# Seperation_Switches.net
KiCad netlist of a schematic drawn in Altium Designer
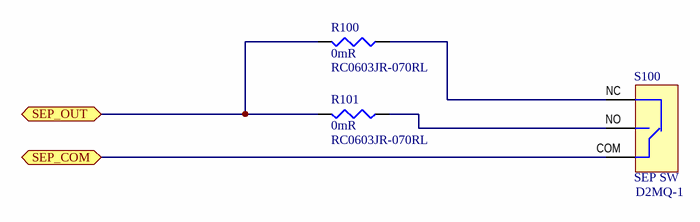
[diagram p0: Seperation Switches.SchDoc]

(export (version "E")
  (design (tool "Eeschema 10.0.6"))
  (components
    (comp (ref "R100")
      (value "0mR")
      (footprint "0603")
      (description "RES SMD 0 OHM JUMPER 1/10W 0603")
      (fields (field (name "MANUFACTURER PART NUMBER 1") "RC0603JR-070RL") (field (name "TOLERANCE") "1%"))
      (libsource (lib "CubeSat-Backplane") (part "RES1"))
    )
    (comp (ref "R101")
      (value "0mR")
      (footprint "0603")
      (description "RES SMD 0 OHM JUMPER 1/10W 0603")
      (fields (field (name "MANUFACTURER PART NUMBER 1") "RC0603JR-070RL") (field (name "TOLERANCE") "1%"))
      (libsource (lib "CubeSat-Backplane") (part "RES1"))
    )
    (comp (ref "S100")
      (value "SEP SW")
      (footprint "D2MQ-1")
      (description "Basic / Snap Action Switches PIN PLUNGER AG-P")
      (fields (field (name "MANUFACTURER") "Omron") (field (name "MANUFACTURER PART NUMBER") "D2MQ-1"))
      (libsource (lib "CubeSat-Backplane") (part "D2MQ-1"))
    )
  )
  (nets
    (net (code "1") (name "/SEP_COM") (class "Default")
      (node (ref "S100") (pin "COM") (pinfunction "COM_COM") (pintype "passive"))
    )
    (net (code "2") (name "/SEP_OUT") (class "Default")
      (node (ref "R100") (pin "2") (pinfunction "2_2") (pintype "passive"))
      (node (ref "R101") (pin "2") (pinfunction "2_2") (pintype "passive"))
    )
    (net (code "3") (name "Net-(R100-Pad1)") (class "Default")
      (node (ref "R100") (pin "1") (pinfunction "1_1") (pintype "passive"))
      (node (ref "S100") (pin "NC") (pinfunction "NC_NC") (pintype "passive"))
    )
    (net (code "4") (name "Net-(R101-Pad1)") (class "Default")
      (node (ref "R101") (pin "1") (pinfunction "1_1") (pintype "passive"))
      (node (ref "S100") (pin "NO") (pinfunction "NO_NO") (pintype "passive"))
    )
  )
)
